# USB_OTG_FS.net
KiCad netlist of a schematic drawn in Altium Designer
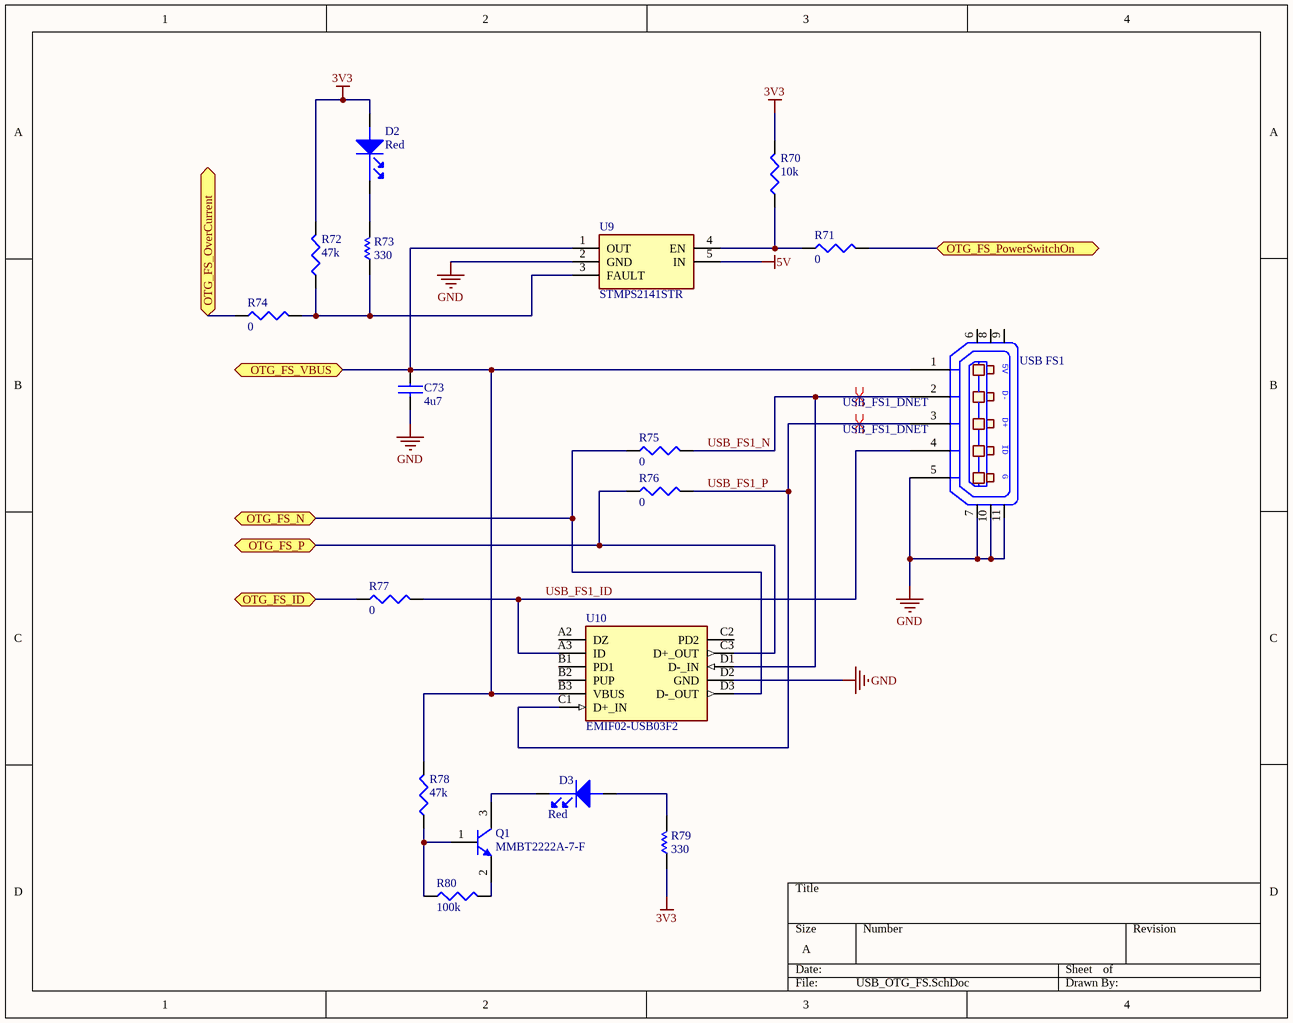
[diagram p0: USB_OTG_FS.SchDoc]

(export (version "E")
  (design (tool "Eeschema 10.0.6"))
  (components
    (comp (ref "C73")
      (value "4u7")
      (footprint "C0402")
      (description "CAP CER 2.2UF 10V 10% X5R 0402")
      (fields
        (field (name "MANUFACTURER") "TDK Corporation")
        (field (name "MANUFACTURER PART NUMBER") "C1005X5R1A225K")
        (field (name ".CHECKED PCB") "RF")
        (field (name ".CHECKED SCH") "RF")
      )
      (libsource (lib "iMX6_Rex_Development_Baseboard_V1I1") (part "C1005X5R1A225K"))
    )
    (comp (ref "D2")
      (value "Red")
      (footprint "LED_0603")
      (description "LED SMARTLED RED 630NM 0603 SMD")
      (fields
        (field (name "MANUFACTURER") "OSRAM Opto Semiconductors Inc")
        (field (name "MANUFACTURER PART NUMBER") "LS L29K-H1J2-1-Z")
        (field (name ".CHECKED PCB") "RF")
        (field (name ".CHECKED SCH") "RF")
      )
      (libsource (lib "iMX6_Rex_Development_Baseboard_V1I1") (part "LS L29K-H1J2-1-Z"))
    )
    (comp (ref "D3")
      (value "Red")
      (footprint "LED_0603")
      (description "LED SMARTLED RED 630NM 0603 SMD")
      (fields
        (field (name "MANUFACTURER") "OSRAM Opto Semiconductors Inc")
        (field (name "MANUFACTURER PART NUMBER") "LS L29K-H1J2-1-Z")
        (field (name ".CHECKED PCB") "RF")
        (field (name ".CHECKED SCH") "RF")
      )
      (libsource (lib "iMX6_Rex_Development_Baseboard_V1I1") (part "LS L29K-H1J2-1-Z"))
    )
    (comp (ref "Q1")
      (value "MMBT2222A-7-F")
      (footprint "DIOD-SOT23-3_V")
      (description "NPN Small Signal Transistor, 40 V, -55 to 150 degC, 3-Pin SOT23, RoHS, Tape and Reel")
      (fields (field (name "MANUFACTURER") "Diodes Inc"))
      (libsource (lib "MiniPC") (part "CMP-1693-00003-1"))
    )
    (comp (ref "R70")
      (value "10k")
      (footprint "R0402")
      (description "RES 10.0K OHM 1/16W 1% 0402 SMD")
      (fields
        (field (name "MANUFACTURER") "Yageo")
        (field (name "MANUFACTURER PART NUMBER") "RC0402FR-0710KL")
      )
      (libsource (lib "iMX6_Rex_Development_Baseboard_V1I1") (part "RC0402FR-0710KL"))
    )
    (comp (ref "R71")
      (value "0")
      (footprint "R0402")
      (description "RES 100 OHM 1/16W 1% 0402 SMD")
      (fields
        (field (name "MANUFACTURER") "Yageo")
        (field (name "MANUFACTURER PART NUMBER") "RC0402FR-07100RL")
        (field (name ".CHECKED PCB") "RF")
        (field (name ".CHECKED SCH") "RF")
      )
      (libsource (lib "iMX6_Rex_Development_Baseboard_V1I1") (part "RC0402FR-07100RL"))
    )
    (comp (ref "R72")
      (value "47k")
      (footprint "R0402")
      (description "RES 10.0K OHM 1/16W 1% 0402 SMD")
      (fields
        (field (name "MANUFACTURER") "Yageo")
        (field (name "MANUFACTURER PART NUMBER") "RC0402FR-0710KL")
      )
      (libsource (lib "iMX6_Rex_Development_Baseboard_V1I1") (part "RC0402FR-0710KL"))
    )
    (comp (ref "R73") (value "330") (footprint "RES 1206") (libsource (lib "L1") (part "RESISTOR")))
    (comp (ref "R74")
      (value "0")
      (footprint "R0402")
      (description "RES 100 OHM 1/16W 1% 0402 SMD")
      (fields
        (field (name "MANUFACTURER") "Yageo")
        (field (name "MANUFACTURER PART NUMBER") "RC0402FR-07100RL")
        (field (name ".CHECKED PCB") "RF")
        (field (name ".CHECKED SCH") "RF")
      )
      (libsource (lib "iMX6_Rex_Development_Baseboard_V1I1") (part "RC0402FR-07100RL"))
    )
    (comp (ref "R75")
      (value "0")
      (footprint "R0402")
      (description "RES 100 OHM 1/16W 1% 0402 SMD")
      (fields
        (field (name "MANUFACTURER") "Yageo")
        (field (name "MANUFACTURER PART NUMBER") "RC0402FR-07100RL")
        (field (name ".CHECKED PCB") "RF")
        (field (name ".CHECKED SCH") "RF")
      )
      (libsource (lib "iMX6_Rex_Development_Baseboard_V1I1") (part "RC0402FR-07100RL"))
    )
    (comp (ref "R76")
      (value "0")
      (footprint "R0402")
      (description "RES 100 OHM 1/16W 1% 0402 SMD")
      (fields
        (field (name "MANUFACTURER") "Yageo")
        (field (name "MANUFACTURER PART NUMBER") "RC0402FR-07100RL")
        (field (name ".CHECKED PCB") "RF")
        (field (name ".CHECKED SCH") "RF")
      )
      (libsource (lib "iMX6_Rex_Development_Baseboard_V1I1") (part "RC0402FR-07100RL"))
    )
    (comp (ref "R77")
      (value "0")
      (footprint "R0402")
      (description "RES 100 OHM 1/16W 1% 0402 SMD")
      (fields
        (field (name "MANUFACTURER") "Yageo")
        (field (name "MANUFACTURER PART NUMBER") "RC0402FR-07100RL")
        (field (name ".CHECKED PCB") "RF")
        (field (name ".CHECKED SCH") "RF")
      )
      (libsource (lib "iMX6_Rex_Development_Baseboard_V1I1") (part "RC0402FR-07100RL"))
    )
    (comp (ref "R78")
      (value "47k")
      (footprint "R0402")
      (description "RES 10.0K OHM 1/16W 1% 0402 SMD")
      (fields
        (field (name "MANUFACTURER") "Yageo")
        (field (name "MANUFACTURER PART NUMBER") "RC0402FR-0710KL")
      )
      (libsource (lib "iMX6_Rex_Development_Baseboard_V1I1") (part "RC0402FR-0710KL"))
    )
    (comp (ref "R79") (value "330") (footprint "RES 1206") (libsource (lib "L1") (part "RESISTOR")))
    (comp (ref "R80")
      (value "100k")
      (footprint "R0402")
      (description "RES 100K OHM 1/16W 1% 0402 SMD")
      (fields
        (field (name "MANUFACTURER") "Stackpole Electronics Inc")
        (field (name "MANUFACTURER PART NUMBER") "RMCF0402FT100K")
      )
      (libsource (lib "iMX6_Rex_Development_Baseboard_V1I1") (part "RMCF0402FT100K"))
    )
    (comp (ref "U9")
      (value "STMPS2141STR")
      (footprint "SamacSys:SOT95P280X145-5N")
      (description "Switch")
      (fields
        (field (name "MOUSER PART NUMBER") "511-STMPS2141STR")
        (field (name "RS PART NUMBER") "8805406P")
      )
      (libsource (lib "*") (part "STMPS2141STR"))
    )
    (comp (ref "U10")
      (value "EMIF02-USB03F2")
      (footprint "SamacSys:BGA11C50P3X4_144X194X72")
      (description "Integrated Circuit")
      (fields
        (field (name "MOUSER PART NUMBER") "511-EMIF02-USB03F2")
        (field (name "RS PART NUMBER") "9172707P")
      )
      (libsource (lib "*") (part "EMIF02-USB03F2"))
    )
    (comp (ref "USB FS1")
      (value "USB MICRO AB")
      (footprint "USB_Micro_AB")
      (description "CONN RCPT MICRO USB AB R/A SMD")
      (fields
        (field (name "MANUFACTURER") "Molex Inc")
        (field (name "MANUFACTURER PART NUMBER") "0475890001")
        (field (name ".CREATOR") "MM")
        (field (name ".CHECKED PCB") "MM")
        (field (name ".CHECKED SCH") "MM")
      )
      (libsource (lib "iMX6_Rex_Development_Baseboard_V1I1") (part "0475890001"))
    )
  )
  (nets
    (net (code "1") (name "/OTG_FS_ID") (class "Default")
      (node (ref "R77") (pin "1") (pinfunction "1_1") (pintype "passive"))
    )
    (net (code "2") (name "/OTG_FS_N") (class "Default")
      (node (ref "R75") (pin "1") (pinfunction "1_1") (pintype "passive"))
      (node (ref "U10") (pin "D3") (pinfunction "D-_OUT_D3") (pintype "output"))
    )
    (net (code "3") (name "/OTG_FS_OverCurrent") (class "Default")
      (node (ref "R74") (pin "1") (pinfunction "1_1") (pintype "passive"))
    )
    (net (code "4") (name "/OTG_FS_P") (class "Default")
      (node (ref "R76") (pin "1") (pinfunction "1_1") (pintype "passive"))
      (node (ref "U10") (pin "C3") (pinfunction "D+_OUT_C3") (pintype "output"))
    )
    (net (code "5") (name "/OTG_FS_PowerSwitchOn") (class "Default")
      (node (ref "R71") (pin "2") (pinfunction "2_2") (pintype "passive"))
    )
    (net (code "6") (name "/OTG_FS_VBUS") (class "Default")
      (node (ref "C73") (pin "1") (pinfunction "1_1") (pintype "passive"))
      (node (ref "R78") (pin "2") (pinfunction "2_2") (pintype "passive"))
      (node (ref "U10") (pin "B3") (pinfunction "VBUS_B3") (pintype "passive"))
      (node (ref "U9") (pin "1") (pinfunction "OUT_1") (pintype "passive"))
      (node (ref "USB FS1") (pin "1") (pinfunction "P1_1") (pintype "passive"))
    )
    (net (code "7") (name "/USB_FS1_ID") (class "Default")
      (node (ref "R77") (pin "2") (pinfunction "2_2") (pintype "passive"))
      (node (ref "U10") (pin "A3") (pinfunction "ID_A3") (pintype "passive"))
      (node (ref "USB FS1") (pin "4") (pinfunction "P4_4") (pintype "passive"))
    )
    (net (code "8") (name "/USB_FS1_N") (class "Default")
      (node (ref "R75") (pin "2") (pinfunction "2_2") (pintype "passive"))
      (node (ref "U10") (pin "D1") (pinfunction "D-_IN_D1") (pintype "input"))
      (node (ref "USB FS1") (pin "2") (pinfunction "P2_2") (pintype "passive"))
    )
    (net (code "9") (name "/USB_FS1_P") (class "Default")
      (node (ref "R76") (pin "2") (pinfunction "2_2") (pintype "passive"))
      (node (ref "U10") (pin "C1") (pinfunction "D+_IN_C1") (pintype "input"))
      (node (ref "USB FS1") (pin "3") (pinfunction "P3_3") (pintype "passive"))
    )
    (net (code "10") (name "3V3") (class "Default")
      (node (ref "D2") (pin "2") (pinfunction "ANODE_2") (pintype "passive"))
      (node (ref "R70") (pin "2") (pinfunction "2_2") (pintype "passive"))
      (node (ref "R72") (pin "2") (pinfunction "2_2") (pintype "passive"))
      (node (ref "R79") (pin "1") (pinfunction "1_1") (pintype "power_in"))
    )
    (net (code "11") (name "5V") (class "Default")
      (node (ref "U9") (pin "5") (pinfunction "IN_5") (pintype "passive"))
    )
    (net (code "12") (name "GND") (class "Default")
      (node (ref "C73") (pin "2") (pinfunction "2_2") (pintype "passive"))
      (node (ref "U10") (pin "D2") (pinfunction "GND_D2") (pintype "power_in"))
      (node (ref "U9") (pin "2") (pinfunction "GND_2") (pintype "passive"))
      (node (ref "USB FS1") (pin "10") (pinfunction "10_10") (pintype "passive"))
      (node (ref "USB FS1") (pin "11") (pinfunction "11_11") (pintype "passive"))
      (node (ref "USB FS1") (pin "5") (pinfunction "P5_5") (pintype "passive"))
      (node (ref "USB FS1") (pin "7") (pinfunction "7_7") (pintype "passive"))
    )
    (net (code "13") (name "Net-(D2-cathode)") (class "Default")
      (node (ref "D2") (pin "1") (pinfunction "cathode_1") (pintype "passive"))
      (node (ref "R73") (pin "2") (pinfunction "2_2") (pintype "power_in"))
    )
    (net (code "14") (name "Net-(D3-ANODE)") (class "Default")
      (node (ref "D3") (pin "2") (pinfunction "ANODE_2") (pintype "passive"))
      (node (ref "R79") (pin "2") (pinfunction "2_2") (pintype "power_in"))
    )
    (net (code "15") (name "Net-(D3-cathode)") (class "Default")
      (node (ref "D3") (pin "1") (pinfunction "cathode_1") (pintype "passive"))
      (node (ref "Q1") (pin "3") (pinfunction "C_3") (pintype "passive"))
    )
    (net (code "16") (name "Net-(Q1-B)") (class "Default")
      (node (ref "Q1") (pin "1") (pinfunction "B_1") (pintype "passive"))
      (node (ref "R78") (pin "1") (pinfunction "1_1") (pintype "passive"))
      (node (ref "R80") (pin "1") (pinfunction "1_1") (pintype "passive"))
    )
    (net (code "17") (name "Net-(Q1-E)") (class "Default")
      (node (ref "Q1") (pin "2") (pinfunction "E_2") (pintype "passive"))
      (node (ref "R80") (pin "2") (pinfunction "2_2") (pintype "passive"))
    )
    (net (code "18") (name "Net-(U9-EN)") (class "Default")
      (node (ref "R70") (pin "1") (pinfunction "1_1") (pintype "passive"))
      (node (ref "R71") (pin "1") (pinfunction "1_1") (pintype "passive"))
      (node (ref "U9") (pin "4") (pinfunction "EN_4") (pintype "passive"))
    )
    (net (code "19") (name "Net-(U9-FAULT)") (class "Default")
      (node (ref "R72") (pin "1") (pinfunction "1_1") (pintype "passive"))
      (node (ref "R73") (pin "1") (pinfunction "1_1") (pintype "power_in"))
      (node (ref "R74") (pin "2") (pinfunction "2_2") (pintype "passive"))
      (node (ref "U9") (pin "3") (pinfunction "FAULT_3") (pintype "passive"))
    )
    (net (code "20") (name "unconnected-(U10-DZ-PadA2)") (class "Default")
      (node (ref "U10") (pin "A2") (pinfunction "DZ_A2") (pintype "passive"))
    )
    (net (code "21") (name "unconnected-(U10-PD1-PadB1)") (class "Default")
      (node (ref "U10") (pin "B1") (pinfunction "PD1_B1") (pintype "passive"))
    )
    (net (code "22") (name "unconnected-(U10-PD2-PadC2)") (class "Default")
      (node (ref "U10") (pin "C2") (pinfunction "PD2_C2") (pintype "passive"))
    )
    (net (code "23") (name "unconnected-(U10-PUP-PadB2)") (class "Default")
      (node (ref "U10") (pin "B2") (pinfunction "PUP_B2") (pintype "passive"))
    )
    (net (code "24") (name "unconnected-(USB FS1-Pad6)") (class "Default")
      (node (ref "USB FS1") (pin "6") (pinfunction "6_6") (pintype "passive"))
    )
    (net (code "25") (name "unconnected-(USB FS1-Pad8)") (class "Default")
      (node (ref "USB FS1") (pin "8") (pinfunction "8_8") (pintype "passive"))
    )
    (net (code "26") (name "unconnected-(USB FS1-Pad9)") (class "Default")
      (node (ref "USB FS1") (pin "9") (pinfunction "9_9") (pintype "passive"))
    )
  )
)
